# board.net
KiCad netlist of a schematic drawn in EAGLE
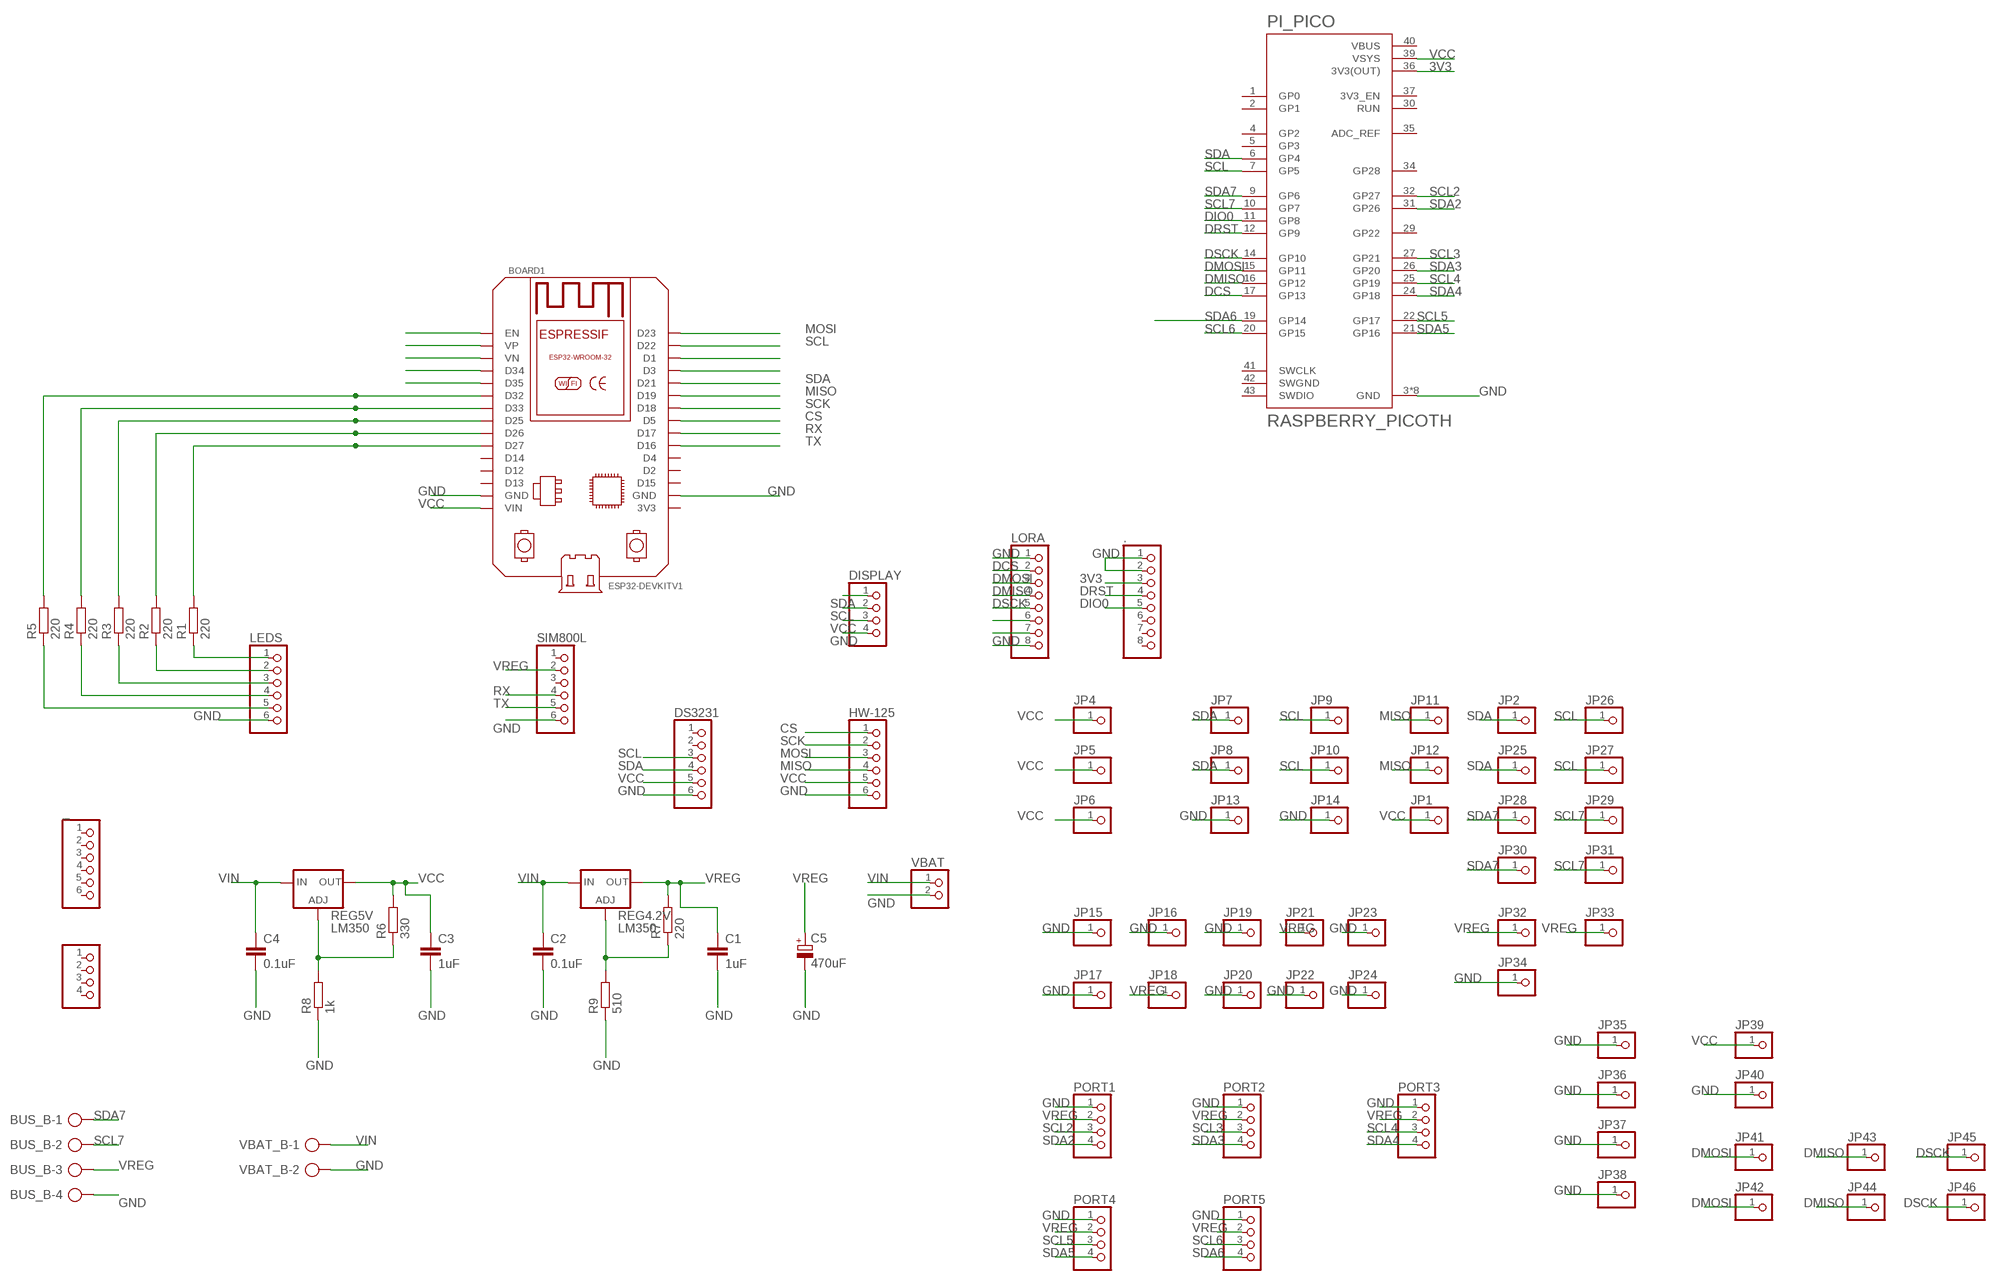
[diagram p0: schematic, sheet 1]

(export (version "E")
  (design (tool "Eeschema 10.0.6"))
  (components
    (comp (ref ".")
      (value "PINHD-1X8")
      (footprint "eagle-import:1X08")
      (libsource (lib "eagle-import") (part "PINHD-1X8"))
    )
    (comp (ref "BOARD1")
      (value "ESP32DEVKITV1")
      (footprint "eagle-import:ESP32-DEVKITV1")
      (libsource (lib "eagle-import") (part "ESP32DEVKITV1"))
    )
    (comp (ref "BUS_B")
      (value "AK500/4-H")
      (footprint "eagle-import:AK500_4-H")
      (libsource (lib "eagle-import") (part "AK500/4-H"))
    )
    (comp (ref "C1")
      (value "1uF")
      (footprint "eagle-import:C2.5-2")
      (libsource (lib "eagle-import") (part "C2.5/2"))
    )
    (comp (ref "C2")
      (value "0.1uF")
      (footprint "eagle-import:C2.5-2")
      (libsource (lib "eagle-import") (part "C2.5/2"))
    )
    (comp (ref "C3")
      (value "1uF")
      (footprint "eagle-import:C2.5-2")
      (libsource (lib "eagle-import") (part "C2.5/2"))
    )
    (comp (ref "C4")
      (value "0.1uF")
      (footprint "eagle-import:C2.5-2")
      (libsource (lib "eagle-import") (part "C2.5/2"))
    )
    (comp (ref "C5")
      (value "470uF")
      (footprint "eagle-import:E3,5-8")
      (libsource (lib "eagle-import") (part "CPOL-EUE3.5-8"))
    )
    (comp (ref "DISPLAY")
      (value "PINHD-1X4")
      (footprint "eagle-import:1X04")
      (libsource (lib "eagle-import") (part "PINHD-1X4"))
    )
    (comp (ref "DS3231")
      (value "PINHD-1X6")
      (footprint "eagle-import:1X06")
      (libsource (lib "eagle-import") (part "PINHD-1X6"))
    )
    (comp (ref "HW-125")
      (value "PINHD-1X6")
      (footprint "eagle-import:1X06")
      (libsource (lib "eagle-import") (part "PINHD-1X6"))
    )
    (comp (ref "JP1")
      (value "PINHD-1X1")
      (footprint "eagle-import:1X01")
      (libsource (lib "eagle-import") (part "PINHD-1X1"))
    )
    (comp (ref "JP2")
      (value "PINHD-1X1")
      (footprint "eagle-import:1X01")
      (libsource (lib "eagle-import") (part "PINHD-1X1"))
    )
    (comp (ref "JP3")
      (value "PINHD-1X4")
      (footprint "eagle-import:1X04")
      (libsource (lib "eagle-import") (part "PINHD-1X4"))
    )
    (comp (ref "JP4")
      (value "PINHD-1X1")
      (footprint "eagle-import:1X01")
      (libsource (lib "eagle-import") (part "PINHD-1X1"))
    )
    (comp (ref "JP5")
      (value "PINHD-1X1")
      (footprint "eagle-import:1X01")
      (libsource (lib "eagle-import") (part "PINHD-1X1"))
    )
    (comp (ref "JP6")
      (value "PINHD-1X1")
      (footprint "eagle-import:1X01")
      (libsource (lib "eagle-import") (part "PINHD-1X1"))
    )
    (comp (ref "JP7")
      (value "PINHD-1X1")
      (footprint "eagle-import:1X01")
      (libsource (lib "eagle-import") (part "PINHD-1X1"))
    )
    (comp (ref "JP8")
      (value "PINHD-1X1")
      (footprint "eagle-import:1X01")
      (libsource (lib "eagle-import") (part "PINHD-1X1"))
    )
    (comp (ref "JP9")
      (value "PINHD-1X1")
      (footprint "eagle-import:1X01")
      (libsource (lib "eagle-import") (part "PINHD-1X1"))
    )
    (comp (ref "JP10")
      (value "PINHD-1X1")
      (footprint "eagle-import:1X01")
      (libsource (lib "eagle-import") (part "PINHD-1X1"))
    )
    (comp (ref "JP11")
      (value "PINHD-1X1")
      (footprint "eagle-import:1X01")
      (libsource (lib "eagle-import") (part "PINHD-1X1"))
    )
    (comp (ref "JP12")
      (value "PINHD-1X1")
      (footprint "eagle-import:1X01")
      (libsource (lib "eagle-import") (part "PINHD-1X1"))
    )
    (comp (ref "JP13")
      (value "PINHD-1X1")
      (footprint "eagle-import:1X01")
      (libsource (lib "eagle-import") (part "PINHD-1X1"))
    )
    (comp (ref "JP14")
      (value "PINHD-1X1")
      (footprint "eagle-import:1X01")
      (libsource (lib "eagle-import") (part "PINHD-1X1"))
    )
    (comp (ref "JP15")
      (value "PINHD-1X1")
      (footprint "eagle-import:1X01")
      (libsource (lib "eagle-import") (part "PINHD-1X1"))
    )
    (comp (ref "JP16")
      (value "PINHD-1X1")
      (footprint "eagle-import:1X01")
      (libsource (lib "eagle-import") (part "PINHD-1X1"))
    )
    (comp (ref "JP17")
      (value "PINHD-1X1")
      (footprint "eagle-import:1X01")
      (libsource (lib "eagle-import") (part "PINHD-1X1"))
    )
    (comp (ref "JP18")
      (value "PINHD-1X1")
      (footprint "eagle-import:1X01")
      (libsource (lib "eagle-import") (part "PINHD-1X1"))
    )
    (comp (ref "JP19")
      (value "PINHD-1X1")
      (footprint "eagle-import:1X01")
      (libsource (lib "eagle-import") (part "PINHD-1X1"))
    )
    (comp (ref "JP20")
      (value "PINHD-1X1")
      (footprint "eagle-import:1X01")
      (libsource (lib "eagle-import") (part "PINHD-1X1"))
    )
    (comp (ref "JP21")
      (value "PINHD-1X1")
      (footprint "eagle-import:1X01")
      (libsource (lib "eagle-import") (part "PINHD-1X1"))
    )
    (comp (ref "JP22")
      (value "PINHD-1X1")
      (footprint "eagle-import:1X01")
      (libsource (lib "eagle-import") (part "PINHD-1X1"))
    )
    (comp (ref "JP23")
      (value "PINHD-1X1")
      (footprint "eagle-import:1X01")
      (libsource (lib "eagle-import") (part "PINHD-1X1"))
    )
    (comp (ref "JP24")
      (value "PINHD-1X1")
      (footprint "eagle-import:1X01")
      (libsource (lib "eagle-import") (part "PINHD-1X1"))
    )
    (comp (ref "JP25")
      (value "PINHD-1X1")
      (footprint "eagle-import:1X01")
      (libsource (lib "eagle-import") (part "PINHD-1X1"))
    )
    (comp (ref "JP26")
      (value "PINHD-1X1")
      (footprint "eagle-import:1X01")
      (libsource (lib "eagle-import") (part "PINHD-1X1"))
    )
    (comp (ref "JP27")
      (value "PINHD-1X1")
      (footprint "eagle-import:1X01")
      (libsource (lib "eagle-import") (part "PINHD-1X1"))
    )
    (comp (ref "JP28")
      (value "PINHD-1X1")
      (footprint "eagle-import:1X01")
      (libsource (lib "eagle-import") (part "PINHD-1X1"))
    )
    (comp (ref "JP29")
      (value "PINHD-1X1")
      (footprint "eagle-import:1X01")
      (libsource (lib "eagle-import") (part "PINHD-1X1"))
    )
    (comp (ref "JP30")
      (value "PINHD-1X1")
      (footprint "eagle-import:1X01")
      (libsource (lib "eagle-import") (part "PINHD-1X1"))
    )
    (comp (ref "JP31")
      (value "PINHD-1X1")
      (footprint "eagle-import:1X01")
      (libsource (lib "eagle-import") (part "PINHD-1X1"))
    )
    (comp (ref "JP32")
      (value "PINHD-1X1")
      (footprint "eagle-import:1X01")
      (libsource (lib "eagle-import") (part "PINHD-1X1"))
    )
    (comp (ref "JP33")
      (value "PINHD-1X1")
      (footprint "eagle-import:1X01")
      (libsource (lib "eagle-import") (part "PINHD-1X1"))
    )
    (comp (ref "JP34")
      (value "PINHD-1X1")
      (footprint "eagle-import:1X01")
      (libsource (lib "eagle-import") (part "PINHD-1X1"))
    )
    (comp (ref "JP35")
      (value "PINHD-1X1")
      (footprint "eagle-import:1X01")
      (libsource (lib "eagle-import") (part "PINHD-1X1"))
    )
    (comp (ref "JP36")
      (value "PINHD-1X1")
      (footprint "eagle-import:1X01")
      (libsource (lib "eagle-import") (part "PINHD-1X1"))
    )
    (comp (ref "JP37")
      (value "PINHD-1X1")
      (footprint "eagle-import:1X01")
      (libsource (lib "eagle-import") (part "PINHD-1X1"))
    )
    (comp (ref "JP38")
      (value "PINHD-1X1")
      (footprint "eagle-import:1X01")
      (libsource (lib "eagle-import") (part "PINHD-1X1"))
    )
    (comp (ref "JP39")
      (value "PINHD-1X1")
      (footprint "eagle-import:1X01")
      (libsource (lib "eagle-import") (part "PINHD-1X1"))
    )
    (comp (ref "JP40")
      (value "PINHD-1X1")
      (footprint "eagle-import:1X01")
      (libsource (lib "eagle-import") (part "PINHD-1X1"))
    )
    (comp (ref "JP41")
      (value "PINHD-1X1")
      (footprint "eagle-import:1X01")
      (libsource (lib "eagle-import") (part "PINHD-1X1"))
    )
    (comp (ref "JP42")
      (value "PINHD-1X1")
      (footprint "eagle-import:1X01")
      (libsource (lib "eagle-import") (part "PINHD-1X1"))
    )
    (comp (ref "JP43")
      (value "PINHD-1X1")
      (footprint "eagle-import:1X01")
      (libsource (lib "eagle-import") (part "PINHD-1X1"))
    )
    (comp (ref "JP44")
      (value "PINHD-1X1")
      (footprint "eagle-import:1X01")
      (libsource (lib "eagle-import") (part "PINHD-1X1"))
    )
    (comp (ref "JP45")
      (value "PINHD-1X1")
      (footprint "eagle-import:1X01")
      (libsource (lib "eagle-import") (part "PINHD-1X1"))
    )
    (comp (ref "JP46")
      (value "PINHD-1X1")
      (footprint "eagle-import:1X01")
      (libsource (lib "eagle-import") (part "PINHD-1X1"))
    )
    (comp (ref "LEDS")
      (value "PINHD-1X6")
      (footprint "eagle-import:1X06")
      (libsource (lib "eagle-import") (part "PINHD-1X6"))
    )
    (comp (ref "LORA")
      (value "PINHD-1X8")
      (footprint "eagle-import:1X08")
      (libsource (lib "eagle-import") (part "PINHD-1X8"))
    )
    (comp (ref "PI_PICO")
      (value "RASPBERRY_PICOTH")
      (footprint "eagle-import:PICO-PKG-TH")
      (libsource (lib "eagle-import") (part "RASPBERRY_PICOTH"))
    )
    (comp (ref "PORT1")
      (value "PINHD-1X4")
      (footprint "eagle-import:1X04")
      (libsource (lib "eagle-import") (part "PINHD-1X4"))
    )
    (comp (ref "PORT2")
      (value "PINHD-1X4")
      (footprint "eagle-import:1X04")
      (libsource (lib "eagle-import") (part "PINHD-1X4"))
    )
    (comp (ref "PORT3")
      (value "PINHD-1X4")
      (footprint "eagle-import:1X04")
      (libsource (lib "eagle-import") (part "PINHD-1X4"))
    )
    (comp (ref "PORT4")
      (value "PINHD-1X4")
      (footprint "eagle-import:1X04")
      (libsource (lib "eagle-import") (part "PINHD-1X4"))
    )
    (comp (ref "PORT5")
      (value "PINHD-1X4")
      (footprint "eagle-import:1X04")
      (libsource (lib "eagle-import") (part "PINHD-1X4"))
    )
    (comp (ref "R1")
      (value "220")
      (footprint "eagle-import:R1206")
      (libsource (lib "eagle-import") (part "R-EU_R1206"))
    )
    (comp (ref "R2")
      (value "220")
      (footprint "eagle-import:R1206")
      (libsource (lib "eagle-import") (part "R-EU_R1206"))
    )
    (comp (ref "R3")
      (value "220")
      (footprint "eagle-import:R1206")
      (libsource (lib "eagle-import") (part "R-EU_R1206"))
    )
    (comp (ref "R4")
      (value "220")
      (footprint "eagle-import:R1206")
      (libsource (lib "eagle-import") (part "R-EU_R1206"))
    )
    (comp (ref "R5")
      (value "220")
      (footprint "eagle-import:R1206")
      (libsource (lib "eagle-import") (part "R-EU_R1206"))
    )
    (comp (ref "R6")
      (value "330")
      (footprint "eagle-import:0204_7")
      (libsource (lib "eagle-import") (part "R-EU_0204/7"))
    )
    (comp (ref "R7")
      (value "220")
      (footprint "eagle-import:0204_7")
      (libsource (lib "eagle-import") (part "R-EU_0204/7"))
    )
    (comp (ref "R8")
      (value "1k")
      (footprint "eagle-import:0204_7")
      (libsource (lib "eagle-import") (part "R-EU_0204/7"))
    )
    (comp (ref "R9")
      (value "510")
      (footprint "eagle-import:0204_7")
      (libsource (lib "eagle-import") (part "R-EU_0204/7"))
    )
    (comp (ref "REG4.2V")
      (value "LM350")
      (footprint "eagle-import:317TS")
      (libsource (lib "eagle-import") (part "LM317TS"))
    )
    (comp (ref "REG5V")
      (value "LM350")
      (footprint "eagle-import:317TS")
      (libsource (lib "eagle-import") (part "LM317TS"))
    )
    (comp (ref "SIM800L")
      (value "PINHD-1X6")
      (footprint "eagle-import:1X06")
      (libsource (lib "eagle-import") (part "PINHD-1X6"))
    )
    (comp (ref "VBAT")
      (value "PINHD-1X2")
      (footprint "eagle-import:1X02")
      (libsource (lib "eagle-import") (part "PINHD-1X2"))
    )
    (comp (ref "VBAT_B")
      (value "AK500/2-H")
      (footprint "eagle-import:AK500_2-H")
      (libsource (lib "eagle-import") (part "AK500/2-H"))
    )
    (comp (ref "_")
      (value "PINHD-1X6")
      (footprint "eagle-import:1X06")
      (libsource (lib "eagle-import") (part "PINHD-1X6"))
    )
  )
  (nets
    (net (code "1") (name "/3V3") (class "Default")
      (node (ref ".") (pin "3") (pinfunction "3_3") (pintype "passive"))
      (node (ref "PI_PICO") (pin "36") (pinfunction "3V3(OUT)_36") (pintype "power_in"))
    )
    (net (code "2") (name "/CS") (class "Default")
      (node (ref "BOARD1") (pin "D5") (pinfunction "D5_D5") (pintype "bidirectional"))
      (node (ref "HW-125") (pin "1") (pinfunction "1_1") (pintype "passive"))
    )
    (net (code "3") (name "/DCS") (class "Default")
      (node (ref "LORA") (pin "2") (pinfunction "2_2") (pintype "passive"))
      (node (ref "PI_PICO") (pin "17") (pinfunction "GP13_17") (pintype "bidirectional"))
    )
    (net (code "4") (name "/DIO0") (class "Default")
      (node (ref ".") (pin "5") (pinfunction "5_5") (pintype "passive"))
      (node (ref "PI_PICO") (pin "11") (pinfunction "GP8_11") (pintype "bidirectional"))
    )
    (net (code "5") (name "/DMISO") (class "Default")
      (node (ref "JP43") (pin "1") (pinfunction "1_1") (pintype "passive"))
      (node (ref "JP44") (pin "1") (pinfunction "1_1") (pintype "passive"))
      (node (ref "LORA") (pin "4") (pinfunction "4_4") (pintype "passive"))
      (node (ref "PI_PICO") (pin "16") (pinfunction "GP12_16") (pintype "bidirectional"))
    )
    (net (code "6") (name "/DMOSI") (class "Default")
      (node (ref "JP41") (pin "1") (pinfunction "1_1") (pintype "passive"))
      (node (ref "JP42") (pin "1") (pinfunction "1_1") (pintype "passive"))
      (node (ref "LORA") (pin "3") (pinfunction "3_3") (pintype "passive"))
      (node (ref "PI_PICO") (pin "15") (pinfunction "GP11_15") (pintype "bidirectional"))
    )
    (net (code "7") (name "/DRST") (class "Default")
      (node (ref ".") (pin "4") (pinfunction "4_4") (pintype "passive"))
      (node (ref "PI_PICO") (pin "12") (pinfunction "GP9_12") (pintype "bidirectional"))
    )
    (net (code "8") (name "/DSCK") (class "Default")
      (node (ref "JP45") (pin "1") (pinfunction "1_1") (pintype "passive"))
      (node (ref "JP46") (pin "1") (pinfunction "1_1") (pintype "passive"))
      (node (ref "LORA") (pin "5") (pinfunction "5_5") (pintype "passive"))
      (node (ref "PI_PICO") (pin "14") (pinfunction "GP10_14") (pintype "bidirectional"))
    )
    (net (code "9") (name "/GND") (class "Default")
      (node (ref ".") (pin "1") (pinfunction "1_1") (pintype "passive"))
      (node (ref ".") (pin "2") (pinfunction "2_2") (pintype "passive"))
      (node (ref "BOARD1") (pin "GND") (pinfunction "GND_GND") (pintype "bidirectional"))
      (node (ref "BOARD1") (pin "GND@1") (pinfunction "GND_GND@1") (pintype "bidirectional"))
      (node (ref "BUS_B") (pin "4") (pinfunction "KL_4") (pintype "passive"))
      (node (ref "C1") (pin "2") (pinfunction "2_2") (pintype "passive"))
      (node (ref "C2") (pin "2") (pinfunction "2_2") (pintype "passive"))
      (node (ref "C3") (pin "2") (pinfunction "2_2") (pintype "passive"))
      (node (ref "C4") (pin "2") (pinfunction "2_2") (pintype "passive"))
      (node (ref "C5") (pin "-") (pinfunction "-_-") (pintype "passive"))
      (node (ref "DISPLAY") (pin "4") (pinfunction "4_4") (pintype "passive"))
      (node (ref "DS3231") (pin "6") (pinfunction "6_6") (pintype "passive"))
      (node (ref "HW-125") (pin "6") (pinfunction "6_6") (pintype "passive"))
      (node (ref "JP13") (pin "1") (pinfunction "1_1") (pintype "passive"))
      (node (ref "JP14") (pin "1") (pinfunction "1_1") (pintype "passive"))
      (node (ref "JP15") (pin "1") (pinfunction "1_1") (pintype "passive"))
      (node (ref "JP16") (pin "1") (pinfunction "1_1") (pintype "passive"))
      (node (ref "JP17") (pin "1") (pinfunction "1_1") (pintype "passive"))
      (node (ref "JP19") (pin "1") (pinfunction "1_1") (pintype "passive"))
      (node (ref "JP20") (pin "1") (pinfunction "1_1") (pintype "passive"))
      (node (ref "JP22") (pin "1") (pinfunction "1_1") (pintype "passive"))
      (node (ref "JP23") (pin "1") (pinfunction "1_1") (pintype "passive"))
      (node (ref "JP24") (pin "1") (pinfunction "1_1") (pintype "passive"))
      (node (ref "JP34") (pin "1") (pinfunction "1_1") (pintype "passive"))
      (node (ref "JP35") (pin "1") (pinfunction "1_1") (pintype "passive"))
      (node (ref "JP36") (pin "1") (pinfunction "1_1") (pintype "passive"))
      (node (ref "JP37") (pin "1") (pinfunction "1_1") (pintype "passive"))
      (node (ref "JP38") (pin "1") (pinfunction "1_1") (pintype "passive"))
      (node (ref "JP40") (pin "1") (pinfunction "1_1") (pintype "passive"))
      (node (ref "LEDS") (pin "6") (pinfunction "6_6") (pintype "passive"))
      (node (ref "LORA") (pin "1") (pinfunction "1_1") (pintype "passive"))
      (node (ref "LORA") (pin "8") (pinfunction "8_8") (pintype "passive"))
      (node (ref "PI_PICO") (pin "13") (pinfunction "GND_13") (pintype "power_in"))
      (node (ref "PI_PICO") (pin "18") (pinfunction "GND_18") (pintype "power_in"))
      (node (ref "PI_PICO") (pin "23") (pinfunction "GND_23") (pintype "power_in"))
      (node (ref "PI_PICO") (pin "28") (pinfunction "GND_28") (pintype "power_in"))
      (node (ref "PI_PICO") (pin "3") (pinfunction "GND_3") (pintype "power_in"))
      (node (ref "PI_PICO") (pin "33") (pinfunction "GND_33") (pintype "power_in"))
      (node (ref "PI_PICO") (pin "38") (pinfunction "GND_38") (pintype "power_in"))
      (node (ref "PI_PICO") (pin "8") (pinfunction "GND_8") (pintype "power_in"))
      (node (ref "PORT1") (pin "1") (pinfunction "1_1") (pintype "passive"))
      (node (ref "PORT2") (pin "1") (pinfunction "1_1") (pintype "passive"))
      (node (ref "PORT3") (pin "1") (pinfunction "1_1") (pintype "passive"))
      (node (ref "PORT4") (pin "1") (pinfunction "1_1") (pintype "passive"))
      (node (ref "PORT5") (pin "1") (pinfunction "1_1") (pintype "passive"))
      (node (ref "R8") (pin "1") (pinfunction "1_1") (pintype "passive"))
      (node (ref "R9") (pin "1") (pinfunction "1_1") (pintype "passive"))
      (node (ref "SIM800L") (pin "6") (pinfunction "6_6") (pintype "passive"))
      (node (ref "VBAT") (pin "2") (pinfunction "2_2") (pintype "passive"))
      (node (ref "VBAT_B") (pin "2") (pinfunction "KL_2") (pintype "passive"))
    )
    (net (code "10") (name "/MISO") (class "Default")
      (node (ref "BOARD1") (pin "D19") (pinfunction "D19_D19") (pintype "bidirectional"))
      (node (ref "HW-125") (pin "4") (pinfunction "4_4") (pintype "passive"))
      (node (ref "JP11") (pin "1") (pinfunction "1_1") (pintype "passive"))
      (node (ref "JP12") (pin "1") (pinfunction "1_1") (pintype "passive"))
    )
    (net (code "11") (name "/MOSI") (class "Default")
      (node (ref "BOARD1") (pin "D23") (pinfunction "D23_D23") (pintype "bidirectional"))
      (node (ref "HW-125") (pin "3") (pinfunction "3_3") (pintype "passive"))
    )
    (net (code "12") (name "/RX") (class "Default")
      (node (ref "BOARD1") (pin "D17") (pinfunction "D17_D17") (pintype "bidirectional"))
      (node (ref "SIM800L") (pin "4") (pinfunction "4_4") (pintype "passive"))
    )
    (net (code "13") (name "/SCK") (class "Default")
      (node (ref "BOARD1") (pin "D18") (pinfunction "D18_D18") (pintype "bidirectional"))
      (node (ref "HW-125") (pin "2") (pinfunction "2_2") (pintype "passive"))
    )
    (net (code "14") (name "/SCL") (class "Default")
      (node (ref "BOARD1") (pin "D22") (pinfunction "D22_D22") (pintype "bidirectional"))
      (node (ref "DISPLAY") (pin "2") (pinfunction "2_2") (pintype "passive"))
      (node (ref "DS3231") (pin "3") (pinfunction "3_3") (pintype "passive"))
      (node (ref "JP10") (pin "1") (pinfunction "1_1") (pintype "passive"))
      (node (ref "JP26") (pin "1") (pinfunction "1_1") (pintype "passive"))
      (node (ref "JP27") (pin "1") (pinfunction "1_1") (pintype "passive"))
      (node (ref "JP9") (pin "1") (pinfunction "1_1") (pintype "passive"))
      (node (ref "PI_PICO") (pin "7") (pinfunction "GP5_7") (pintype "bidirectional"))
    )
    (net (code "15") (name "/SCL2") (class "Default")
      (node (ref "PI_PICO") (pin "32") (pinfunction "GP27_32") (pintype "bidirectional"))
      (node (ref "PORT1") (pin "3") (pinfunction "3_3") (pintype "passive"))
    )
    (net (code "16") (name "/SCL3") (class "Default")
      (node (ref "PI_PICO") (pin "27") (pinfunction "GP21_27") (pintype "bidirectional"))
      (node (ref "PORT2") (pin "3") (pinfunction "3_3") (pintype "passive"))
    )
    (net (code "17") (name "/SCL4") (class "Default")
      (node (ref "PI_PICO") (pin "25") (pinfunction "GP19_25") (pintype "bidirectional"))
      (node (ref "PORT3") (pin "3") (pinfunction "3_3") (pintype "passive"))
    )
    (net (code "18") (name "/SCL5") (class "Default")
      (node (ref "PI_PICO") (pin "22") (pinfunction "GP17_22") (pintype "bidirectional"))
      (node (ref "PORT4") (pin "3") (pinfunction "3_3") (pintype "passive"))
    )
    (net (code "19") (name "/SCL6") (class "Default")
      (node (ref "PI_PICO") (pin "20") (pinfunction "GP15_20") (pintype "bidirectional"))
      (node (ref "PORT5") (pin "3") (pinfunction "3_3") (pintype "passive"))
    )
    (net (code "20") (name "/SCL7") (class "Default")
      (node (ref "BUS_B") (pin "2") (pinfunction "KL_2") (pintype "passive"))
      (node (ref "JP29") (pin "1") (pinfunction "1_1") (pintype "passive"))
      (node (ref "JP31") (pin "1") (pinfunction "1_1") (pintype "passive"))
      (node (ref "PI_PICO") (pin "10") (pinfunction "GP7_10") (pintype "bidirectional"))
    )
    (net (code "21") (name "/SDA") (class "Default")
      (node (ref "BOARD1") (pin "D21") (pinfunction "D21_D21") (pintype "bidirectional"))
      (node (ref "DISPLAY") (pin "1") (pinfunction "1_1") (pintype "passive"))
      (node (ref "DS3231") (pin "4") (pinfunction "4_4") (pintype "passive"))
      (node (ref "JP2") (pin "1") (pinfunction "1_1") (pintype "passive"))
      (node (ref "JP25") (pin "1") (pinfunction "1_1") (pintype "passive"))
      (node (ref "JP7") (pin "1") (pinfunction "1_1") (pintype "passive"))
      (node (ref "JP8") (pin "1") (pinfunction "1_1") (pintype "passive"))
      (node (ref "PI_PICO") (pin "6") (pinfunction "GP4_6") (pintype "bidirectional"))
    )
    (net (code "22") (name "/SDA2") (class "Default")
      (node (ref "PI_PICO") (pin "31") (pinfunction "GP26_31") (pintype "bidirectional"))
      (node (ref "PORT1") (pin "4") (pinfunction "4_4") (pintype "passive"))
    )
    (net (code "23") (name "/SDA3") (class "Default")
      (node (ref "PI_PICO") (pin "26") (pinfunction "GP20_26") (pintype "bidirectional"))
      (node (ref "PORT2") (pin "4") (pinfunction "4_4") (pintype "passive"))
    )
    (net (code "24") (name "/SDA4") (class "Default")
      (node (ref "PI_PICO") (pin "24") (pinfunction "GP18_24") (pintype "bidirectional"))
      (node (ref "PORT3") (pin "4") (pinfunction "4_4") (pintype "passive"))
    )
    (net (code "25") (name "/SDA5") (class "Default")
      (node (ref "PI_PICO") (pin "21") (pinfunction "GP16_21") (pintype "bidirectional"))
      (node (ref "PORT4") (pin "4") (pinfunction "4_4") (pintype "passive"))
    )
    (net (code "26") (name "/SDA6") (class "Default")
      (node (ref "PI_PICO") (pin "19") (pinfunction "GP14_19") (pintype "bidirectional"))
      (node (ref "PORT5") (pin "4") (pinfunction "4_4") (pintype "passive"))
    )
    (net (code "27") (name "/SDA7") (class "Default")
      (node (ref "BUS_B") (pin "1") (pinfunction "KL_1") (pintype "passive"))
      (node (ref "JP28") (pin "1") (pinfunction "1_1") (pintype "passive"))
      (node (ref "JP30") (pin "1") (pinfunction "1_1") (pintype "passive"))
      (node (ref "PI_PICO") (pin "9") (pinfunction "GP6_9") (pintype "bidirectional"))
    )
    (net (code "28") (name "/SWGND") (class "Default")
      (node (ref "PI_PICO") (pin "42") (pinfunction "SWGND_42") (pintype "power_in"))
    )
    (net (code "29") (name "/TX") (class "Default")
      (node (ref "BOARD1") (pin "D16") (pinfunction "D16_D16") (pintype "bidirectional"))
      (node (ref "SIM800L") (pin "5") (pinfunction "5_5") (pintype "passive"))
    )
    (net (code "30") (name "/VBUS") (class "Default")
      (node (ref "PI_PICO") (pin "40") (pinfunction "VBUS_40") (pintype "power_in"))
    )
    (net (code "31") (name "/VCC") (class "Default")
      (node (ref "BOARD1") (pin "VIN") (pinfunction "VIN_VIN") (pintype "bidirectional"))
      (node (ref "C3") (pin "1") (pinfunction "1_1") (pintype "passive"))
      (node (ref "DISPLAY") (pin "3") (pinfunction "3_3") (pintype "passive"))
      (node (ref "DS3231") (pin "5") (pinfunction "5_5") (pintype "passive"))
      (node (ref "HW-125") (pin "5") (pinfunction "5_5") (pintype "passive"))
      (node (ref "JP1") (pin "1") (pinfunction "1_1") (pintype "passive"))
      (node (ref "JP39") (pin "1") (pinfunction "1_1") (pintype "passive"))
      (node (ref "JP4") (pin "1") (pinfunction "1_1") (pintype "passive"))
      (node (ref "JP5") (pin "1") (pinfunction "1_1") (pintype "passive"))
      (node (ref "JP6") (pin "1") (pinfunction "1_1") (pintype "passive"))
      (node (ref "PI_PICO") (pin "39") (pinfunction "VSYS_39") (pintype "power_in"))
      (node (ref "R6") (pin "2") (pinfunction "2_2") (pintype "passive"))
      (node (ref "REG5V") (pin "2") (pinfunction "OUT_2") (pintype "passive"))
    )
    (net (code "32") (name "/VIN") (class "Default")
      (node (ref "C2") (pin "1") (pinfunction "1_1") (pintype "passive"))
      (node (ref "C4") (pin "1") (pinfunction "1_1") (pintype "passive"))
      (node (ref "REG4.2V") (pin "3") (pinfunction "IN_3") (pintype "input"))
      (node (ref "REG5V") (pin "3") (pinfunction "IN_3") (pintype "input"))
      (node (ref "VBAT") (pin "1") (pinfunction "1_1") (pintype "passive"))
      (node (ref "VBAT_B") (pin "1") (pinfunction "KL_1") (pintype "passive"))
    )
    (net (code "33") (name "/VREG") (class "Default")
      (node (ref "BUS_B") (pin "3") (pinfunction "KL_3") (pintype "passive"))
      (node (ref "C1") (pin "1") (pinfunction "1_1") (pintype "passive"))
      (node (ref "C5") (pin "+") (pinfunction "+_+") (pintype "passive"))
      (node (ref "JP18") (pin "1") (pinfunction "1_1") (pintype "passive"))
      (node (ref "JP21") (pin "1") (pinfunction "1_1") (pintype "passive"))
      (node (ref "JP32") (pin "1") (pinfunction "1_1") (pintype "passive"))
      (node (ref "JP33") (pin "1") (pinfunction "1_1") (pintype "passive"))
      (node (ref "PORT1") (pin "2") (pinfunction "2_2") (pintype "passive"))
      (node (ref "PORT2") (pin "2") (pinfunction "2_2") (pintype "passive"))
      (node (ref "PORT3") (pin "2") (pinfunction "2_2") (pintype "passive"))
      (node (ref "PORT4") (pin "2") (pinfunction "2_2") (pintype "passive"))
      (node (ref "PORT5") (pin "2") (pinfunction "2_2") (pintype "passive"))
      (node (ref "R7") (pin "2") (pinfunction "2_2") (pintype "passive"))
      (node (ref "REG4.2V") (pin "2") (pinfunction "OUT_2") (pintype "passive"))
      (node (ref "SIM800L") (pin "2") (pinfunction "2_2") (pintype "passive"))
    )
    (net (code "34") (name "Net-(BOARD1-PadD25)") (class "Default")
      (node (ref "BOARD1") (pin "D25") (pinfunction "D25_D25") (pintype "bidirectional"))
      (node (ref "R3") (pin "2") (pinfunction "2_2") (pintype "passive"))
    )
    (net (code "35") (name "Net-(BOARD1-PadD26)") (class "Default")
      (node (ref "BOARD1") (pin "D26") (pinfunction "D26_D26") (pintype "bidirectional"))
      (node (ref "R2") (pin "2") (pinfunction "2_2") (pintype "passive"))
    )
    (net (code "36") (name "Net-(BOARD1-PadD27)") (class "Default")
      (node (ref "BOARD1") (pin "D27") (pinfunction "D27_D27") (pintype "bidirectional"))
      (node (ref "R1") (pin "2") (pinfunction "2_2") (pintype "passive"))
    )
    (net (code "37") (name "Net-(BOARD1-PadD32)") (class "Default")
      (node (ref "BOARD1") (pin "D32") (pinfunction "D32_D32") (pintype "bidirectional"))
      (node (ref "R5") (pin "2") (pinfunction "2_2") (pintype "passive"))
    )
    (net (code "38") (name "Net-(BOARD1-PadD33)") (class "Default")
      (node (ref "BOARD1") (pin "D33") (pinfunction "D33_D33") (pintype "bidirectional"))
      (node (ref "R4") (pin "2") (pinfunction "2_2") (pintype "passive"))
    )
    (net (code "39") (name "Net-(LEDS-Pad1)") (class "Default")
      (node (ref "LEDS") (pin "1") (pinfunction "1_1") (pintype "passive"))
      (node (ref "R1") (pin "1") (pinfunction "1_1") (pintype "passive"))
    )
    (net (code "40") (name "Net-(LEDS-Pad2)") (class "Default")
      (node (ref "LEDS") (pin "2") (pinfunction "2_2") (pintype "passive"))
      (node (ref "R2") (pin "1") (pinfunction "1_1") (pintype "passive"))
    )
    (net (code "41") (name "Net-(LEDS-Pad3)") (class "Default")
      (node (ref "LEDS") (pin "3") (pinfunction "3_3") (pintype "passive"))
      (node (ref "R3") (pin "1") (pinfunction "1_1") (pintype "passive"))
    )
    (net (code "42") (name "Net-(LEDS-Pad4)") (class "Default")
      (node (ref "LEDS") (pin "4") (pinfunction "4_4") (pintype "passive"))
      (node (ref "R4") (pin "1") (pinfunction "1_1") (pintype "passive"))
    )
    (net (code "43") (name "Net-(LEDS-Pad5)") (class "Default")
      (node (ref "LEDS") (pin "5") (pinfunction "5_5") (pintype "passive"))
      (node (ref "R5") (pin "1") (pinfunction "1_1") (pintype "passive"))
    )
    (net (code "44") (name "Net-(REG4.2V-ADJ)") (class "Default")
      (node (ref "R7") (pin "1") (pinfunction "1_1") (pintype "passive"))
      (node (ref "R9") (pin "2") (pinfunction "2_2") (pintype "passive"))
      (node (ref "REG4.2V") (pin "1") (pinfunction "ADJ_1") (pintype "input"))
    )
    (net (code "45") (name "Net-(REG5V-ADJ)") (class "Default")
      (node (ref "R6") (pin "1") (pinfunction "1_1") (pintype "passive"))
      (node (ref "R8") (pin "2") (pinfunction "2_2") (pintype "passive"))
      (node (ref "REG5V") (pin "1") (pinfunction "ADJ_1") (pintype "input"))
    )
    (net (code "46") (name "unconnected-(.-Pad6)") (class "Default")
      (node (ref ".") (pin "6") (pinfunction "6_6") (pintype "passive"))
    )
    (net (code "47") (name "unconnected-(.-Pad7)") (class "Default")
      (node (ref ".") (pin "7") (pinfunction "7_7") (pintype "passive"))
    )
    (net (code "48") (name "unconnected-(.-Pad8)") (class "Default")
      (node (ref ".") (pin "8") (pinfunction "8_8") (pintype "passive"))
    )
    (net (code "49") (name "unconnected-(BOARD1-Pad3V3)") (class "Default")
      (node (ref "BOARD1") (pin "3V3") (pinfunction "3V3_3V3") (pintype "bidirectional"))
    )
    (net (code "50") (name "unconnected-(BOARD1-PadD1)") (class "Default")
      (node (ref "BOARD1") (pin "D1") (pinfunction "D1_D1") (pintype "bidirectional"))
    )
    (net (code "51") (name "unconnected-(BOARD1-PadD2)") (class "Default")
      (node (ref "BOARD1") (pin "D2") (pinfunction "D2_D2") (pintype "bidirectional"))
    )
    (net (code "52") (name "unconnected-(BOARD1-PadD3)") (class "Default")
      (node (ref "BOARD1") (pin "D3") (pinfunction "D3_D3") (pintype "bidirectional"))
    )
    (net (code "53") (name "unconnected-(BOARD1-PadD4)") (class "Default")
      (node (ref "BOARD1") (pin "D4") (pinfunction "D4_D4") (pintype "bidirectional"))
    )
    (net (code "54") (name "unconnected-(BOARD1-PadD12)") (class "Default")
      (node (ref "BOARD1") (pin "D12") (pinfunction "D12_D12") (pintype "bidirectional"))
    )
    (net (code "55") (name "unconnected-(BOARD1-PadD13)") (class "Default")
      (node (ref "BOARD1") (pin "D13") (pinfunction "D13_D13") (pintype "bidirectional"))
    )
    (net (code "56") (name "unconnected-(BOARD1-PadD14)") (class "Default")
      (node (ref "BOARD1") (pin "D14") (pinfunction "D14_D14") (pintype "bidirectional"))
    )
    (net (code "57") (name "unconnected-(BOARD1-PadD15)") (class "Default")
      (node (ref "BOARD1") (pin "D15") (pinfunction "D15_D15") (pintype "bidirectional"))
    )
    (net (code "58") (name "unconnected-(BOARD1-PadD34)") (class "Default")
      (node (ref "BOARD1") (pin "D34") (pinfunction "D34_D34") (pintype "bidirectional"))
    )
    (net (code "59") (name "unconnected-(BOARD1-PadD35)") (class "Default")
      (node (ref "BOARD1") (pin "D35") (pinfunction "D35_D35") (pintype "bidirectional"))
    )
    (net (code "60") (name "unconnected-(BOARD1-PadEN)") (class "Default")
      (node (ref "BOARD1") (pin "EN") (pinfunction "EN_EN") (pintype "bidirectional"))
    )
    (net (code "61") (name "unconnected-(BOARD1-PadVN)") (class "Default")
      (node (ref "BOARD1") (pin "VN") (pinfunction "VN_VN") (pintype "bidirectional"))
    )
    (net (code "62") (name "unconnected-(BOARD1-PadVP)") (class "Default")
      (node (ref "BOARD1") (pin "VP") (pinfunction "VP_VP") (pintype "bidirectional"))
    )
    (net (code "63") (name "unconnected-(DS3231-Pad1)") (class "Default")
      (node (ref "DS3231") (pin "1") (pinfunction "1_1") (pintype "passive"))
    )
    (net (code "64") (name "unconnected-(DS3231-Pad2)") (class "Default")
      (node (ref "DS3231") (pin "2") (pinfunction "2_2") (pintype "passive"))
    )
    (net (code "65") (name "unconnected-(JP3-Pad1)") (class "Default")
      (node (ref "JP3") (pin "1") (pinfunction "1_1") (pintype "passive"))
    )
    (net (code "66") (name "unconnected-(JP3-Pad2)") (class "Default")
      (node (ref "JP3") (pin "2") (pinfunction "2_2") (pintype "passive"))
    )
    (net (code "67") (name "unconnected-(JP3-Pad3)") (class "Default")
      (node (ref "JP3") (pin "3") (pinfunction "3_3") (pintype "passive"))
    )
    (net (code "68") (name "unconnected-(JP3-Pad4)") (class "Default")
      (node (ref "JP3") (pin "4") (pinfunction "4_4") (pintype "passive"))
    )
    (net (code "69") (name "unconnected-(LORA-Pad6)") (class "Default")
      (node (ref "LORA") (pin "6") (pinfunction "6_6") (pintype "passive"))
    )
    (net (code "70") (name "unconnected-(LORA-Pad7)") (class "Default")
      (node (ref "LORA") (pin "7") (pinfunction "7_7") (pintype "passive"))
    )
    (net (code "71") (name "unconnected-(PI_PICO-3V3_EN-Pad37)") (class "Default")
      (node (ref "PI_PICO") (pin "37") (pinfunction "3V3_EN_37") (pintype "input"))
    )
    (net (code "72") (name "unconnected-(PI_PICO-ADC_REF-Pad35)") (class "Default")
      (node (ref "PI_PICO") (pin "35") (pinfunction "ADC_REF_35") (pintype "input"))
    )
    (net (code "73") (name "unconnected-(PI_PICO-GP0-Pad1)") (class "Default")
      (node (ref "PI_PICO") (pin "1") (pinfunction "GP0_1") (pintype "bidirectional"))
    )
    (net (code "74") (name "unconnected-(PI_PICO-GP1-Pad2)") (class "Default")
      (node (ref "PI_PICO") (pin "2") (pinfunction "GP1_2") (pintype "bidirectional"))
    )
    (net (code "75") (name "unconnected-(PI_PICO-GP2-Pad4)") (class "Default")
      (node (ref "PI_PICO") (pin "4") (pinfunction "GP2_4") (pintype "bidirectional"))
    )
    (net (code "76") (name "unconnected-(PI_PICO-GP3-Pad5)") (class "Default")
      (node (ref "PI_PICO") (pin "5") (pinfunction "GP3_5") (pintype "bidirectional"))
    )
    (net (code "77") (name "unconnected-(PI_PICO-GP22-Pad29)") (class "Default")
      (node (ref "PI_PICO") (pin "29") (pinfunction "GP22_29") (pintype "bidirectional"))
    )
    (net (code "78") (name "unconnected-(PI_PICO-GP28-Pad34)") (class "Default")
      (node (ref "PI_PICO") (pin "34") (pinfunction "GP28_34") (pintype "bidirectional"))
    )
    (net (code "79") (name "unconnected-(PI_PICO-RUN-Pad30)") (class "Default")
      (node (ref "PI_PICO") (pin "30") (pinfunction "RUN_30") (pintype "input"))
    )
    (net (code "80") (name "unconnected-(PI_PICO-SWCLK-Pad41)") (class "Default")
      (node (ref "PI_PICO") (pin "41") (pinfunction "SWCLK_41") (pintype "input"))
    )
    (net (code "81") (name "unconnected-(PI_PICO-SWDIO-Pad43)") (class "Default")
      (node (ref "PI_PICO") (pin "43") (pinfunction "SWDIO_43") (pintype "bidirectional"))
    )
    (net (code "82") (name "unconnected-(SIM800L-Pad1)") (class "Default")
      (node (ref "SIM800L") (pin "1") (pinfunction "1_1") (pintype "passive"))
    )
    (net (code "83") (name "unconnected-(SIM800L-Pad3)") (class "Default")
      (node (ref "SIM800L") (pin "3") (pinfunction "3_3") (pintype "passive"))
    )
    (net (code "84") (name "unconnected-(_-Pad1)") (class "Default")
      (node (ref "_") (pin "1") (pinfunction "1_1") (pintype "passive"))
    )
    (net (code "85") (name "unconnected-(_-Pad2)") (class "Default")
      (node (ref "_") (pin "2") (pinfunction "2_2") (pintype "passive"))
    )
    (net (code "86") (name "unconnected-(_-Pad3)") (class "Default")
      (node (ref "_") (pin "3") (pinfunction "3_3") (pintype "passive"))
    )
    (net (code "87") (name "unconnected-(_-Pad4)") (class "Default")
      (node (ref "_") (pin "4") (pinfunction "4_4") (pintype "passive"))
    )
    (net (code "88") (name "unconnected-(_-Pad5)") (class "Default")
      (node (ref "_") (pin "5") (pinfunction "5_5") (pintype "passive"))
    )
    (net (code "89") (name "unconnected-(_-Pad6)") (class "Default")
      (node (ref "_") (pin "6") (pinfunction "6_6") (pintype "passive"))
    )
  )
)
